# Demo_CW6655A_SSOP20_BLE_V1_2.net
KiCad netlist of a schematic drawn in Altium Designer
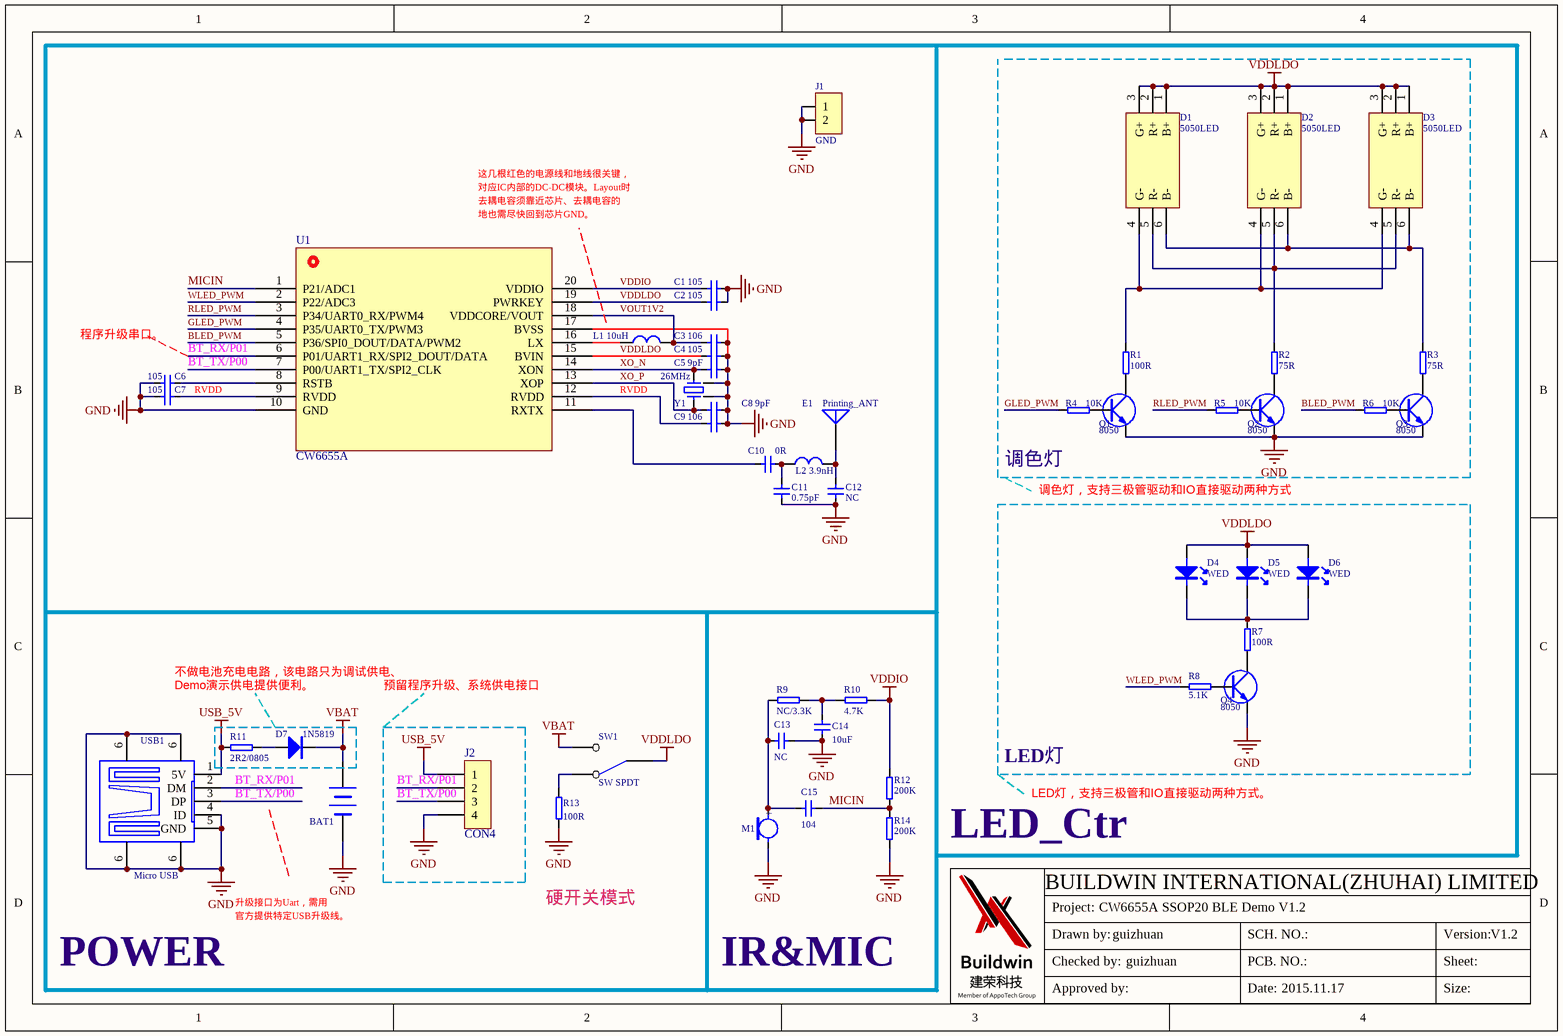
[diagram p0: Demo CW6655A SSOP20 BLE V1.2.SchDoc]

(export (version "E")
  (design (tool "Eeschema 10.0.6"))
  (components
    (comp (ref "BAT1")
      (value "排针")
      (footprint "sip2")
      (description "Battery")
      (libsource (lib "*") (part "BATTERY"))
    )
    (comp (ref "C1")
      (value "105")
      (footprint "C0603")
      (description "Capacitor")
      (libsource (lib "") (part "CAP_1"))
    )
    (comp (ref "C2")
      (value "105")
      (footprint "C0603")
      (description "Capacitor")
      (libsource (lib "") (part "CAP_1"))
    )
    (comp (ref "C3")
      (value "106")
      (footprint "C0805")
      (description "Capacitor")
      (libsource (lib "") (part "CAP_1"))
    )
    (comp (ref "C4")
      (value "105")
      (footprint "C0603")
      (description "Capacitor")
      (libsource (lib "") (part "CAP_1"))
    )
    (comp (ref "C5")
      (value "9pF")
      (footprint "C0603")
      (description "Capacitor")
      (libsource (lib "") (part "CAP_1"))
    )
    (comp (ref "C6")
      (value "105")
      (footprint "c0603")
      (description "Capacitor")
      (libsource (lib "") (part "CAP_1"))
    )
    (comp (ref "C7")
      (value "105")
      (footprint "C0603")
      (description "Capacitor")
      (libsource (lib "") (part "CAP_1"))
    )
    (comp (ref "C8")
      (value "9pF")
      (footprint "C0603")
      (description "Capacitor")
      (libsource (lib "") (part "CAP_1"))
    )
    (comp (ref "C9")
      (value "106")
      (footprint "C0603")
      (description "Capacitor")
      (libsource (lib "") (part "CAP_1"))
    )
    (comp (ref "C10")
      (value "0R")
      (footprint "c0603")
      (description "Capacitor")
      (libsource (lib "") (part "CAP_1"))
    )
    (comp (ref "C11")
      (value "0.75pF")
      (footprint "C0603")
      (description "Capacitor")
      (libsource (lib "*") (part "CAP"))
    )
    (comp (ref "C12")
      (value "NC")
      (footprint "C0603")
      (description "Capacitor")
      (libsource (lib "*") (part "CAP"))
    )
    (comp (ref "C13")
      (value "NC")
      (footprint "C0603")
      (description "Capacitor")
      (libsource (lib "Common SCH") (part "CAP"))
    )
    (comp (ref "C14")
      (value "10uF")
      (footprint "C0805")
      (description "Capacitor")
      (libsource (lib "Common SCH") (part "CAP"))
    )
    (comp (ref "C15")
      (value "104")
      (footprint "C0603")
      (description "Capacitor")
      (libsource (lib "Common SCH") (part "CAP"))
    )
    (comp (ref "D1") (value "5050LED") (footprint "5050LED") (libsource (lib "BuildwinYGZ") (part "5050LED")))
    (comp (ref "D2") (value "5050LED") (footprint "5050LED") (libsource (lib "BuildwinYGZ") (part "5050LED")))
    (comp (ref "D3")
      (value "5050LED")
      (footprint "5050LED")
      (libsource (lib "AX3281 LQFP64 WIFI Boombox Demo V1.0") (part "5050LED"))
    )
    (comp (ref "D4") (value "WED") (footprint "D3528") (libsource (lib "*") (part "LED")))
    (comp (ref "D5") (value "WED") (footprint "D3528") (libsource (lib "*") (part "LED")))
    (comp (ref "D6") (value "WED") (footprint "D3528") (libsource (lib "*") (part "LED")))
    (comp (ref "D7")
      (value "1N5819")
      (footprint "DO-214")
      (description "Diode")
      (libsource (lib "*") (part "DIODE"))
    )
    (comp (ref "E1")
      (value "Printing_ANT")
      (footprint "IFA")
      (description "Generic Antenna")
      (fields (field (name "PUBLISHER") "Altium Limited"))
      (libsource (lib "*") (part "Antenna"))
    )
    (comp (ref "J1")
      (value "GND")
      (footprint "SIP2")
      (description "Connector")
      (libsource (lib "*") (part "CON2"))
    )
    (comp (ref "J2")
      (value "CON4")
      (footprint "SIP4")
      (description "Connector")
      (libsource (lib "Common SCH") (part "CON4"))
    )
    (comp (ref "L1") (value "10uH") (footprint "L0805") (libsource (lib "*") (part "INDUCTOR")))
    (comp (ref "L2") (value "3.9nH") (footprint "L0603") (libsource (lib "*") (part "INDUCTOR")))
    (comp (ref "M1")
      (value "MIC")
      (footprint "MIC")
      (description "Microphone")
      (libsource (lib "*") (part "MICROPHONE2"))
    )
    (comp (ref "Q1")
      (value "8050")
      (footprint "SOT-23")
      (description "NPN Transistor")
      (libsource (lib "*") (part "NPN-SMD1"))
    )
    (comp (ref "Q2")
      (value "8050")
      (footprint "SOT-23")
      (description "NPN Transistor")
      (libsource (lib "*") (part "NPN-SMD1"))
    )
    (comp (ref "Q3")
      (value "8050")
      (footprint "SOT-23")
      (description "NPN Transistor")
      (libsource (lib "*") (part "NPN-SMD1"))
    )
    (comp (ref "Q4")
      (value "8050")
      (footprint "SOT-23")
      (description "NPN Transistor")
      (libsource (lib "*") (part "NPN-SMD1"))
    )
    (comp (ref "R1") (value "100R") (footprint "R0603") (libsource (lib "Common SCH") (part "RES2")))
    (comp (ref "R2") (value "75R") (footprint "R0603") (libsource (lib "Common SCH") (part "RES2")))
    (comp (ref "R3") (value "75R") (footprint "R0603") (libsource (lib "Common SCH") (part "RES2")))
    (comp (ref "R4") (value "10K") (footprint "R0603") (libsource (lib "Common SCH") (part "RES2")))
    (comp (ref "R5") (value "10K") (footprint "R0603") (libsource (lib "Common SCH") (part "RES2")))
    (comp (ref "R6") (value "10K") (footprint "R0603") (libsource (lib "Common SCH") (part "RES2")))
    (comp (ref "R7") (value "100R") (footprint "R0603") (libsource (lib "Common SCH") (part "RES2")))
    (comp (ref "R8") (value "5.1K") (footprint "R0603") (libsource (lib "Common SCH") (part "RES2")))
    (comp (ref "R9") (value "NC/3.3K") (footprint "R0603") (libsource (lib "Common SCH") (part "RES2")))
    (comp (ref "R10") (value "4.7K") (footprint "R0603") (libsource (lib "Common SCH") (part "RES2")))
    (comp (ref "R11") (value "2R2/0805") (footprint "R0805") (libsource (lib "Common SCH") (part "RES2")))
    (comp (ref "R12") (value "200K") (footprint "R0603") (libsource (lib "Common SCH") (part "RES2")))
    (comp (ref "R13") (value "100R") (footprint "R0603") (libsource (lib "Common SCH") (part "RES2")))
    (comp (ref "R14") (value "200K") (footprint "R0603") (libsource (lib "Common SCH") (part "RES2")))
    (comp (ref "SW1")
      (value "SW SPDT")
      (footprint "SWWDIP")
      (libsource (lib "AX2227 CW6637 SPI DEMO V0.1") (part "SW SPDT"))
    )
    (comp (ref "U1")
      (value "CW6655A")
      (footprint "SSOP_20L")
      (libsource (lib "BuildwinYGZ") (part "CW6655A"))
    )
    (comp (ref "USB1")
      (value "Micro USB")
      (footprint "USB-MICRO")
      (libsource (lib "BW SCH") (part "Mini USB-F"))
    )
    (comp (ref "Y1") (value "26MHz") (footprint "26m") (libsource (lib "*") (part "CRYSTAL")))
  )
  (nets
    (net (code "1") (name "/BLED_PWM") (class "Default")
      (node (ref "R6") (pin "2") (pinfunction "2_2") (pintype "passive"))
      (node (ref "U1") (pin "5") (pinfunction "P36/SPI0_DOUT/DATA/PWM2_5") (pintype "passive"))
    )
    (net (code "2") (name "/BT_RX{slash}P01") (class "Default")
      (node (ref "J2") (pin "2") (pinfunction "2_2") (pintype "passive"))
      (node (ref "U1") (pin "6") (pinfunction "P01/UART1_RX/SPI2_DOUT/DATA_6") (pintype "passive"))
      (node (ref "USB1") (pin "2") (pinfunction "DM_2") (pintype "passive"))
    )
    (net (code "3") (name "/BT_TX{slash}P00") (class "Default")
      (node (ref "J2") (pin "3") (pinfunction "3_3") (pintype "passive"))
      (node (ref "U1") (pin "7") (pinfunction "P00/UART1_TX/SPI2_CLK_7") (pintype "passive"))
      (node (ref "USB1") (pin "3") (pinfunction "DP_3") (pintype "passive"))
    )
    (net (code "4") (name "/GLED_PWM") (class "Default")
      (node (ref "R4") (pin "2") (pinfunction "2_2") (pintype "passive"))
      (node (ref "U1") (pin "4") (pinfunction "P35/UART0_TX/PWM3_4") (pintype "passive"))
    )
    (net (code "5") (name "/MICIN") (class "Default")
      (node (ref "C15") (pin "1") (pinfunction "1_1") (pintype "passive"))
      (node (ref "R12") (pin "1") (pinfunction "1_1") (pintype "passive"))
      (node (ref "R14") (pin "2") (pinfunction "2_2") (pintype "passive"))
      (node (ref "U1") (pin "1") (pinfunction "P21/ADC1_1") (pintype "passive"))
    )
    (net (code "6") (name "/RLED_PWM") (class "Default")
      (node (ref "R5") (pin "2") (pinfunction "2_2") (pintype "passive"))
      (node (ref "U1") (pin "3") (pinfunction "P34/UART0_RX/PWM4_3") (pintype "passive"))
    )
    (net (code "7") (name "/RVDD") (class "Default")
      (node (ref "C7") (pin "1") (pinfunction "1_1") (pintype "passive"))
      (node (ref "C9") (pin "2") (pinfunction "2_2") (pintype "passive"))
      (node (ref "U1") (pin "12") (pinfunction "RVDD_12") (pintype "passive"))
      (node (ref "U1") (pin "9") (pinfunction "RVDD_9") (pintype "passive"))
    )
    (net (code "8") (name "/VOUT1V2") (class "Default")
      (node (ref "C3") (pin "2") (pinfunction "2_2") (pintype "passive"))
      (node (ref "L1") (pin "2") (pinfunction "2_2") (pintype "passive"))
      (node (ref "U1") (pin "18") (pinfunction "VDDCORE/VOUT_18") (pintype "passive"))
    )
    (net (code "9") (name "/WLED_PWM") (class "Default")
      (node (ref "R8") (pin "2") (pinfunction "2_2") (pintype "passive"))
      (node (ref "U1") (pin "2") (pinfunction "P22/ADC3_2") (pintype "passive"))
    )
    (net (code "10") (name "/XO_N") (class "Default")
      (node (ref "C5") (pin "2") (pinfunction "2_2") (pintype "passive"))
      (node (ref "U1") (pin "14") (pinfunction "XON_14") (pintype "passive"))
      (node (ref "Y1") (pin "3") (pinfunction "3_3") (pintype "passive"))
    )
    (net (code "11") (name "/XO_P") (class "Default")
      (node (ref "C8") (pin "2") (pinfunction "2_2") (pintype "passive"))
      (node (ref "U1") (pin "13") (pinfunction "XOP_13") (pintype "passive"))
      (node (ref "Y1") (pin "1") (pinfunction "1_1") (pintype "passive"))
    )
    (net (code "12") (name "GND") (class "Default")
      (node (ref "BAT1") (pin "2") (pinfunction "-_2") (pintype "passive"))
      (node (ref "C1") (pin "1") (pinfunction "1_1") (pintype "passive"))
      (node (ref "C11") (pin "1") (pinfunction "1_1") (pintype "passive"))
      (node (ref "C12") (pin "1") (pinfunction "1_1") (pintype "passive"))
      (node (ref "C13") (pin "1") (pinfunction "1_1") (pintype "passive"))
      (node (ref "C14") (pin "1") (pinfunction "1_1") (pintype "passive"))
      (node (ref "C2") (pin "1") (pinfunction "1_1") (pintype "passive"))
      (node (ref "C3") (pin "1") (pinfunction "1_1") (pintype "passive"))
      (node (ref "C4") (pin "1") (pinfunction "1_1") (pintype "passive"))
      (node (ref "C5") (pin "1") (pinfunction "1_1") (pintype "passive"))
      (node (ref "C6") (pin "2") (pinfunction "2_2") (pintype "passive"))
      (node (ref "C7") (pin "2") (pinfunction "2_2") (pintype "passive"))
      (node (ref "C8") (pin "1") (pinfunction "1_1") (pintype "passive"))
      (node (ref "C9") (pin "1") (pinfunction "1_1") (pintype "passive"))
      (node (ref "J1") (pin "1") (pinfunction "1_1") (pintype "passive"))
      (node (ref "J1") (pin "2") (pinfunction "2_2") (pintype "passive"))
      (node (ref "J2") (pin "4") (pinfunction "4_4") (pintype "passive"))
      (node (ref "M1") (pin "2") (pinfunction "2_2") (pintype "passive"))
      (node (ref "Q1") (pin "2") (pinfunction "E_2") (pintype "passive"))
      (node (ref "Q2") (pin "2") (pinfunction "E_2") (pintype "passive"))
      (node (ref "Q3") (pin "2") (pinfunction "E_2") (pintype "passive"))
      (node (ref "Q4") (pin "2") (pinfunction "E_2") (pintype "passive"))
      (node (ref "R13") (pin "2") (pinfunction "2_2") (pintype "passive"))
      (node (ref "R14") (pin "1") (pinfunction "1_1") (pintype "passive"))
      (node (ref "U1") (pin "10") (pinfunction "GND_10") (pintype "passive"))
      (node (ref "U1") (pin "17") (pinfunction "BVSS_17") (pintype "passive"))
      (node (ref "USB1") (pin "4") (pinfunction "ID_4") (pintype "passive"))
      (node (ref "USB1") (pin "5") (pinfunction "GND_5") (pintype "passive"))
      (node (ref "USB1") (pin "6") (pintype "passive"))
      (node (ref "Y1") (pin "2") (pinfunction "2_2") (pintype "passive"))
      (node (ref "Y1") (pin "4") (pinfunction "4_4") (pintype "passive"))
    )
    (net (code "13") (name "Net-(C10-Pad2)") (class "Default")
      (node (ref "C10") (pin "2") (pinfunction "2_2") (pintype "passive"))
      (node (ref "C11") (pin "2") (pinfunction "2_2") (pintype "passive"))
      (node (ref "L2") (pin "1") (pinfunction "1_1") (pintype "passive"))
    )
    (net (code "14") (name "Net-(C13-Pad2)") (class "Default")
      (node (ref "C13") (pin "2") (pinfunction "2_2") (pintype "passive"))
      (node (ref "C15") (pin "2") (pinfunction "2_2") (pintype "passive"))
      (node (ref "M1") (pin "1") (pinfunction "1_1") (pintype "passive"))
      (node (ref "R9") (pin "1") (pinfunction "1_1") (pintype "passive"))
    )
    (net (code "15") (name "Net-(C14-Pad2)") (class "Default")
      (node (ref "C14") (pin "2") (pinfunction "2_2") (pintype "passive"))
      (node (ref "R10") (pin "1") (pinfunction "1_1") (pintype "passive"))
      (node (ref "R9") (pin "2") (pinfunction "2_2") (pintype "passive"))
    )
    (net (code "16") (name "Net-(D1-B-)") (class "Default")
      (node (ref "D1") (pin "6") (pinfunction "B-_6") (pintype "passive"))
      (node (ref "D2") (pin "6") (pinfunction "B-_6") (pintype "passive"))
      (node (ref "D3") (pin "6") (pinfunction "B-_6") (pintype "passive"))
      (node (ref "R3") (pin "1") (pinfunction "1_1") (pintype "passive"))
    )
    (net (code "17") (name "Net-(D1-G-)") (class "Default")
      (node (ref "D1") (pin "4") (pinfunction "G-_4") (pintype "passive"))
      (node (ref "D2") (pin "4") (pinfunction "G-_4") (pintype "passive"))
      (node (ref "D3") (pin "4") (pinfunction "G-_4") (pintype "passive"))
      (node (ref "R1") (pin "1") (pinfunction "1_1") (pintype "passive"))
    )
    (net (code "18") (name "Net-(D1-R-)") (class "Default")
      (node (ref "D1") (pin "5") (pinfunction "R-_5") (pintype "passive"))
      (node (ref "D2") (pin "5") (pinfunction "R-_5") (pintype "passive"))
      (node (ref "D3") (pin "5") (pinfunction "R-_5") (pintype "passive"))
      (node (ref "R2") (pin "1") (pinfunction "1_1") (pintype "passive"))
    )
    (net (code "19") (name "Net-(D4-Pad2)") (class "Default")
      (node (ref "D4") (pin "2") (pinfunction "2_2") (pintype "passive"))
      (node (ref "D5") (pin "2") (pinfunction "2_2") (pintype "passive"))
      (node (ref "D6") (pin "2") (pinfunction "2_2") (pintype "passive"))
      (node (ref "R7") (pin "2") (pinfunction "2_2") (pintype "passive"))
    )
    (net (code "20") (name "Net-(D7-A)") (class "Default")
      (node (ref "D7") (pin "1") (pinfunction "A_1") (pintype "passive"))
      (node (ref "R11") (pin "2") (pinfunction "2_2") (pintype "passive"))
    )
    (net (code "21") (name "Net-(E1-A)") (class "Default")
      (node (ref "C12") (pin "2") (pinfunction "2_2") (pintype "passive"))
      (node (ref "E1") (pin "1") (pinfunction "A_1") (pintype "passive"))
      (node (ref "L2") (pin "2") (pinfunction "2_2") (pintype "passive"))
    )
    (net (code "22") (name "Net-(Q1-B)") (class "Default")
      (node (ref "Q1") (pin "1") (pinfunction "B_1") (pintype "passive"))
      (node (ref "R4") (pin "1") (pinfunction "1_1") (pintype "passive"))
    )
    (net (code "23") (name "Net-(Q1-C)") (class "Default")
      (node (ref "Q1") (pin "3") (pinfunction "C_3") (pintype "passive"))
      (node (ref "R1") (pin "2") (pinfunction "2_2") (pintype "passive"))
    )
    (net (code "24") (name "Net-(Q2-B)") (class "Default")
      (node (ref "Q2") (pin "1") (pinfunction "B_1") (pintype "passive"))
      (node (ref "R5") (pin "1") (pinfunction "1_1") (pintype "passive"))
    )
    (net (code "25") (name "Net-(Q2-C)") (class "Default")
      (node (ref "Q2") (pin "3") (pinfunction "C_3") (pintype "passive"))
      (node (ref "R2") (pin "2") (pinfunction "2_2") (pintype "passive"))
    )
    (net (code "26") (name "Net-(Q3-B)") (class "Default")
      (node (ref "Q3") (pin "1") (pinfunction "B_1") (pintype "passive"))
      (node (ref "R6") (pin "1") (pinfunction "1_1") (pintype "passive"))
    )
    (net (code "27") (name "Net-(Q3-C)") (class "Default")
      (node (ref "Q3") (pin "3") (pinfunction "C_3") (pintype "passive"))
      (node (ref "R3") (pin "2") (pinfunction "2_2") (pintype "passive"))
    )
    (net (code "28") (name "Net-(Q4-B)") (class "Default")
      (node (ref "Q4") (pin "1") (pinfunction "B_1") (pintype "passive"))
      (node (ref "R8") (pin "1") (pinfunction "1_1") (pintype "passive"))
    )
    (net (code "29") (name "Net-(Q4-C)") (class "Default")
      (node (ref "Q4") (pin "3") (pinfunction "C_3") (pintype "passive"))
      (node (ref "R7") (pin "1") (pinfunction "1_1") (pintype "passive"))
    )
    (net (code "30") (name "Net-(SW1-NC)") (class "Default")
      (node (ref "R13") (pin "1") (pinfunction "1_1") (pintype "passive"))
      (node (ref "SW1") (pin "2") (pinfunction "NC_2") (pintype "passive"))
    )
    (net (code "31") (name "Net-(U1-LX)") (class "Default")
      (node (ref "L1") (pin "1") (pinfunction "1_1") (pintype "passive"))
      (node (ref "U1") (pin "16") (pinfunction "LX_16") (pintype "passive"))
    )
    (net (code "32") (name "Net-(U1-RSTB)") (class "Default")
      (node (ref "C6") (pin "1") (pinfunction "1_1") (pintype "passive"))
      (node (ref "U1") (pin "8") (pinfunction "RSTB_8") (pintype "passive"))
    )
    (net (code "33") (name "Net-(U1-RXTX)") (class "Default")
      (node (ref "C10") (pin "1") (pinfunction "1_1") (pintype "passive"))
      (node (ref "U1") (pin "11") (pinfunction "RXTX_11") (pintype "passive"))
    )
    (net (code "34") (name "USB_5V") (class "Default")
      (node (ref "J2") (pin "1") (pinfunction "1_1") (pintype "passive"))
      (node (ref "R11") (pin "1") (pinfunction "1_1") (pintype "passive"))
      (node (ref "USB1") (pin "1") (pinfunction "5V_1") (pintype "passive"))
    )
    (net (code "35") (name "VBAT") (class "Default")
      (node (ref "BAT1") (pin "1") (pinfunction "+_1") (pintype "passive"))
      (node (ref "D7") (pin "2") (pinfunction "K_2") (pintype "passive"))
      (node (ref "SW1") (pin "3") (pinfunction "NO_3") (pintype "passive"))
    )
    (net (code "36") (name "VDDIO") (class "Default")
      (node (ref "C1") (pin "2") (pinfunction "2_2") (pintype "passive"))
      (node (ref "R10") (pin "2") (pinfunction "2_2") (pintype "passive"))
      (node (ref "R12") (pin "2") (pinfunction "2_2") (pintype "passive"))
      (node (ref "U1") (pin "20") (pinfunction "VDDIO_20") (pintype "passive"))
    )
    (net (code "37") (name "VDDLDO") (class "Default")
      (node (ref "C2") (pin "2") (pinfunction "2_2") (pintype "passive"))
      (node (ref "C4") (pin "2") (pinfunction "2_2") (pintype "passive"))
      (node (ref "D1") (pin "1") (pinfunction "B+_1") (pintype "passive"))
      (node (ref "D1") (pin "2") (pinfunction "R+_2") (pintype "passive"))
      (node (ref "D1") (pin "3") (pinfunction "G+_3") (pintype "passive"))
      (node (ref "D2") (pin "1") (pinfunction "B+_1") (pintype "passive"))
      (node (ref "D2") (pin "2") (pinfunction "R+_2") (pintype "passive"))
      (node (ref "D2") (pin "3") (pinfunction "G+_3") (pintype "passive"))
      (node (ref "D3") (pin "1") (pinfunction "B+_1") (pintype "passive"))
      (node (ref "D3") (pin "2") (pinfunction "R+_2") (pintype "passive"))
      (node (ref "D3") (pin "3") (pinfunction "G+_3") (pintype "passive"))
      (node (ref "D4") (pin "1") (pinfunction "1_1") (pintype "passive"))
      (node (ref "D5") (pin "1") (pinfunction "1_1") (pintype "passive"))
      (node (ref "D6") (pin "1") (pinfunction "1_1") (pintype "passive"))
      (node (ref "SW1") (pin "1") (pinfunction "COMMON_1") (pintype "passive"))
      (node (ref "U1") (pin "15") (pinfunction "BVIN_15") (pintype "passive"))
      (node (ref "U1") (pin "19") (pinfunction "PWRKEY_19") (pintype "passive"))
    )
  )
)
